# ProPrj_zmk-afa_2025-04-29.net
KiCad netlist of a schematic drawn in EasyEDA Pro
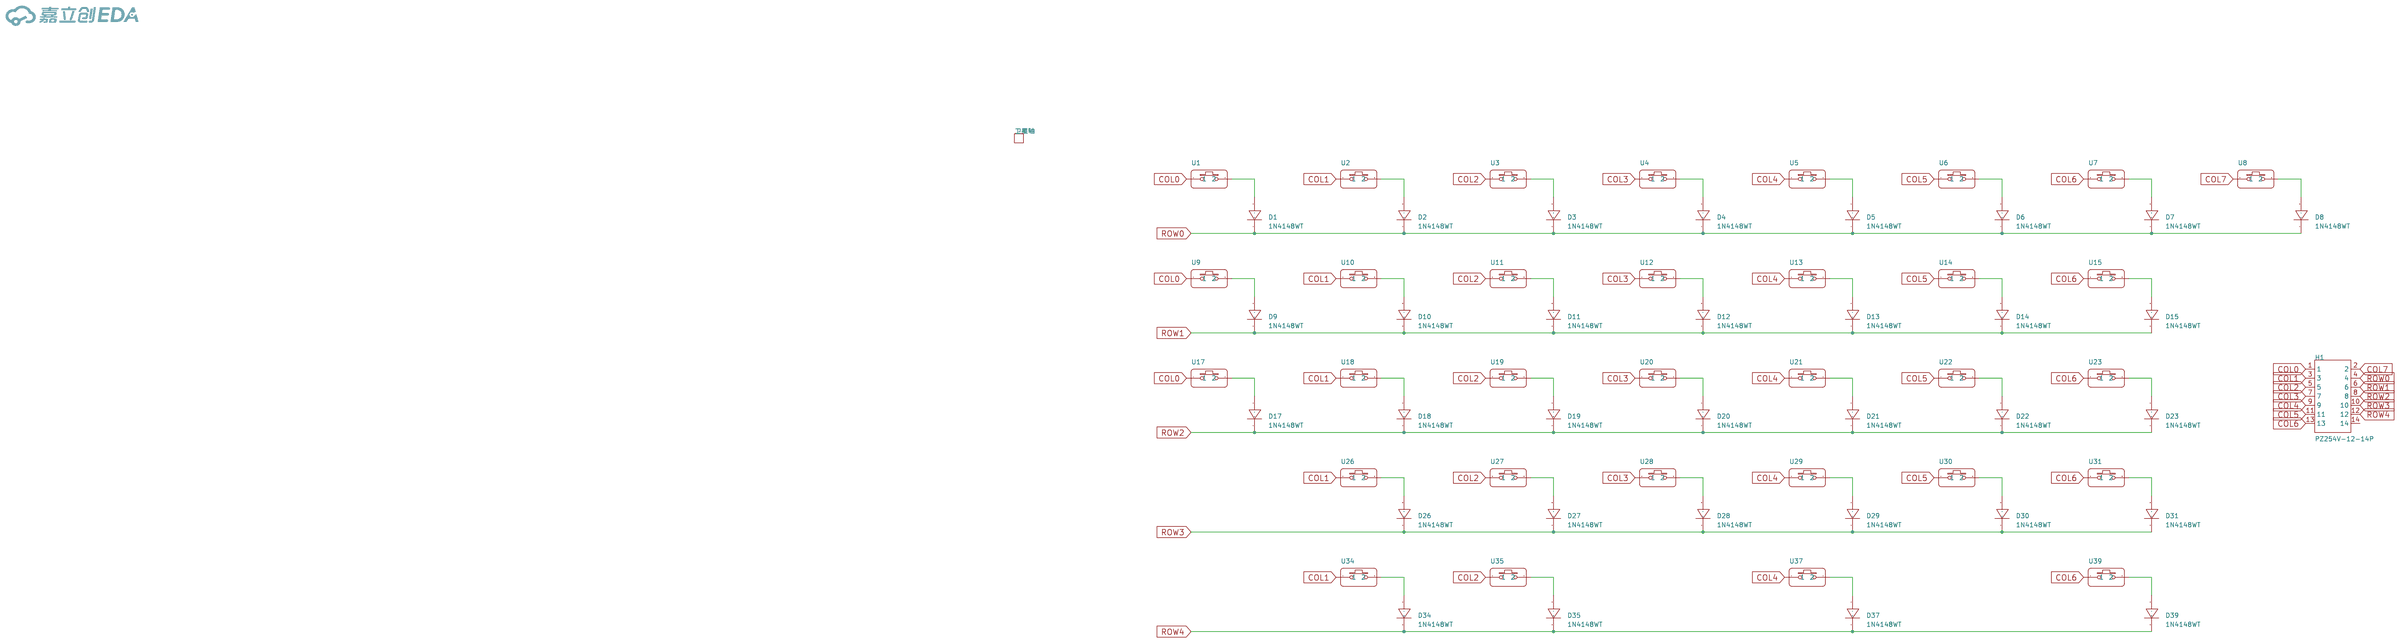
[diagram p0: schematic sheet]

(export (version "E")
  (design (tool "Eeschema 10.0.6"))
  (components
    (comp (ref "D1")
      (value "1N4148WT")
      (footprint "easyedapro:SOD-523_L1.2-W0.8-LS1.6-RD")
      (description "二极管配置:独立式;正向压降(Vf):1V@10mA;直流反向耐压(Vr):75V;整流电流:300mA;反向恢复时间(trr):4ns;")
      (fields (field (name "Manufacturer") "onsemi(安森美)"))
      (libsource (lib "easyedapro") (part "1N4148WT_C232841"))
    )
    (comp (ref "D2")
      (value "1N4148WT")
      (footprint "easyedapro:SOD-523_L1.2-W0.8-LS1.6-RD")
      (description "二极管配置:独立式;正向压降(Vf):1V@10mA;直流反向耐压(Vr):75V;整流电流:300mA;反向恢复时间(trr):4ns;")
      (fields (field (name "Manufacturer") "onsemi(安森美)"))
      (libsource (lib "easyedapro") (part "1N4148WT_C232841"))
    )
    (comp (ref "D3")
      (value "1N4148WT")
      (footprint "easyedapro:SOD-523_L1.2-W0.8-LS1.6-RD")
      (description "二极管配置:独立式;正向压降(Vf):1V@10mA;直流反向耐压(Vr):75V;整流电流:300mA;反向恢复时间(trr):4ns;")
      (fields (field (name "Manufacturer") "onsemi(安森美)"))
      (libsource (lib "easyedapro") (part "1N4148WT_C232841"))
    )
    (comp (ref "D4")
      (value "1N4148WT")
      (footprint "easyedapro:SOD-523_L1.2-W0.8-LS1.6-RD")
      (description "二极管配置:独立式;正向压降(Vf):1V@10mA;直流反向耐压(Vr):75V;整流电流:300mA;反向恢复时间(trr):4ns;")
      (fields (field (name "Manufacturer") "onsemi(安森美)"))
      (libsource (lib "easyedapro") (part "1N4148WT_C232841"))
    )
    (comp (ref "D5")
      (value "1N4148WT")
      (footprint "easyedapro:SOD-523_L1.2-W0.8-LS1.6-RD")
      (description "二极管配置:独立式;正向压降(Vf):1V@10mA;直流反向耐压(Vr):75V;整流电流:300mA;反向恢复时间(trr):4ns;")
      (fields (field (name "Manufacturer") "onsemi(安森美)"))
      (libsource (lib "easyedapro") (part "1N4148WT_C232841"))
    )
    (comp (ref "D6")
      (value "1N4148WT")
      (footprint "easyedapro:SOD-523_L1.2-W0.8-LS1.6-RD")
      (description "二极管配置:独立式;正向压降(Vf):1V@10mA;直流反向耐压(Vr):75V;整流电流:300mA;反向恢复时间(trr):4ns;")
      (fields (field (name "Manufacturer") "onsemi(安森美)"))
      (libsource (lib "easyedapro") (part "1N4148WT_C232841"))
    )
    (comp (ref "D7")
      (value "1N4148WT")
      (footprint "easyedapro:SOD-523_L1.2-W0.8-LS1.6-RD")
      (description "二极管配置:独立式;正向压降(Vf):1V@10mA;直流反向耐压(Vr):75V;整流电流:300mA;反向恢复时间(trr):4ns;")
      (fields (field (name "Manufacturer") "onsemi(安森美)"))
      (libsource (lib "easyedapro") (part "1N4148WT_C232841"))
    )
    (comp (ref "D8")
      (value "1N4148WT")
      (footprint "easyedapro:SOD-523_L1.2-W0.8-LS1.6-RD")
      (description "二极管配置:独立式;正向压降(Vf):1V@10mA;直流反向耐压(Vr):75V;整流电流:300mA;反向恢复时间(trr):4ns;")
      (fields (field (name "Manufacturer") "onsemi(安森美)"))
      (libsource (lib "easyedapro") (part "1N4148WT_C232841"))
    )
    (comp (ref "D9")
      (value "1N4148WT")
      (footprint "easyedapro:SOD-523_L1.2-W0.8-LS1.6-RD")
      (description "二极管配置:独立式;正向压降(Vf):1V@10mA;直流反向耐压(Vr):75V;整流电流:300mA;反向恢复时间(trr):4ns;")
      (fields (field (name "Manufacturer") "onsemi(安森美)"))
      (libsource (lib "easyedapro") (part "1N4148WT_C232841"))
    )
    (comp (ref "D10")
      (value "1N4148WT")
      (footprint "easyedapro:SOD-523_L1.2-W0.8-LS1.6-RD")
      (description "二极管配置:独立式;正向压降(Vf):1V@10mA;直流反向耐压(Vr):75V;整流电流:300mA;反向恢复时间(trr):4ns;")
      (fields (field (name "Manufacturer") "onsemi(安森美)"))
      (libsource (lib "easyedapro") (part "1N4148WT_C232841"))
    )
    (comp (ref "D11")
      (value "1N4148WT")
      (footprint "easyedapro:SOD-523_L1.2-W0.8-LS1.6-RD")
      (description "二极管配置:独立式;正向压降(Vf):1V@10mA;直流反向耐压(Vr):75V;整流电流:300mA;反向恢复时间(trr):4ns;")
      (fields (field (name "Manufacturer") "onsemi(安森美)"))
      (libsource (lib "easyedapro") (part "1N4148WT_C232841"))
    )
    (comp (ref "D12")
      (value "1N4148WT")
      (footprint "easyedapro:SOD-523_L1.2-W0.8-LS1.6-RD")
      (description "二极管配置:独立式;正向压降(Vf):1V@10mA;直流反向耐压(Vr):75V;整流电流:300mA;反向恢复时间(trr):4ns;")
      (fields (field (name "Manufacturer") "onsemi(安森美)"))
      (libsource (lib "easyedapro") (part "1N4148WT_C232841"))
    )
    (comp (ref "D13")
      (value "1N4148WT")
      (footprint "easyedapro:SOD-523_L1.2-W0.8-LS1.6-RD")
      (description "二极管配置:独立式;正向压降(Vf):1V@10mA;直流反向耐压(Vr):75V;整流电流:300mA;反向恢复时间(trr):4ns;")
      (fields (field (name "Manufacturer") "onsemi(安森美)"))
      (libsource (lib "easyedapro") (part "1N4148WT_C232841"))
    )
    (comp (ref "D14")
      (value "1N4148WT")
      (footprint "easyedapro:SOD-523_L1.2-W0.8-LS1.6-RD")
      (description "二极管配置:独立式;正向压降(Vf):1V@10mA;直流反向耐压(Vr):75V;整流电流:300mA;反向恢复时间(trr):4ns;")
      (fields (field (name "Manufacturer") "onsemi(安森美)"))
      (libsource (lib "easyedapro") (part "1N4148WT_C232841"))
    )
    (comp (ref "D15")
      (value "1N4148WT")
      (footprint "easyedapro:SOD-523_L1.2-W0.8-LS1.6-RD")
      (description "二极管配置:独立式;正向压降(Vf):1V@10mA;直流反向耐压(Vr):75V;整流电流:300mA;反向恢复时间(trr):4ns;")
      (fields (field (name "Manufacturer") "onsemi(安森美)"))
      (libsource (lib "easyedapro") (part "1N4148WT_C232841"))
    )
    (comp (ref "D17")
      (value "1N4148WT")
      (footprint "easyedapro:SOD-523_L1.2-W0.8-LS1.6-RD")
      (description "二极管配置:独立式;正向压降(Vf):1V@10mA;直流反向耐压(Vr):75V;整流电流:300mA;反向恢复时间(trr):4ns;")
      (fields (field (name "Manufacturer") "onsemi(安森美)"))
      (libsource (lib "easyedapro") (part "1N4148WT_C232841"))
    )
    (comp (ref "D18")
      (value "1N4148WT")
      (footprint "easyedapro:SOD-523_L1.2-W0.8-LS1.6-RD")
      (description "二极管配置:独立式;正向压降(Vf):1V@10mA;直流反向耐压(Vr):75V;整流电流:300mA;反向恢复时间(trr):4ns;")
      (fields (field (name "Manufacturer") "onsemi(安森美)"))
      (libsource (lib "easyedapro") (part "1N4148WT_C232841"))
    )
    (comp (ref "D19")
      (value "1N4148WT")
      (footprint "easyedapro:SOD-523_L1.2-W0.8-LS1.6-RD")
      (description "二极管配置:独立式;正向压降(Vf):1V@10mA;直流反向耐压(Vr):75V;整流电流:300mA;反向恢复时间(trr):4ns;")
      (fields (field (name "Manufacturer") "onsemi(安森美)"))
      (libsource (lib "easyedapro") (part "1N4148WT_C232841"))
    )
    (comp (ref "D20")
      (value "1N4148WT")
      (footprint "easyedapro:SOD-523_L1.2-W0.8-LS1.6-RD")
      (description "二极管配置:独立式;正向压降(Vf):1V@10mA;直流反向耐压(Vr):75V;整流电流:300mA;反向恢复时间(trr):4ns;")
      (fields (field (name "Manufacturer") "onsemi(安森美)"))
      (libsource (lib "easyedapro") (part "1N4148WT_C232841"))
    )
    (comp (ref "D21")
      (value "1N4148WT")
      (footprint "easyedapro:SOD-523_L1.2-W0.8-LS1.6-RD")
      (description "二极管配置:独立式;正向压降(Vf):1V@10mA;直流反向耐压(Vr):75V;整流电流:300mA;反向恢复时间(trr):4ns;")
      (fields (field (name "Manufacturer") "onsemi(安森美)"))
      (libsource (lib "easyedapro") (part "1N4148WT_C232841"))
    )
    (comp (ref "D22")
      (value "1N4148WT")
      (footprint "easyedapro:SOD-523_L1.2-W0.8-LS1.6-RD")
      (description "二极管配置:独立式;正向压降(Vf):1V@10mA;直流反向耐压(Vr):75V;整流电流:300mA;反向恢复时间(trr):4ns;")
      (fields (field (name "Manufacturer") "onsemi(安森美)"))
      (libsource (lib "easyedapro") (part "1N4148WT_C232841"))
    )
    (comp (ref "D23")
      (value "1N4148WT")
      (footprint "easyedapro:SOD-523_L1.2-W0.8-LS1.6-RD")
      (description "二极管配置:独立式;正向压降(Vf):1V@10mA;直流反向耐压(Vr):75V;整流电流:300mA;反向恢复时间(trr):4ns;")
      (fields (field (name "Manufacturer") "onsemi(安森美)"))
      (libsource (lib "easyedapro") (part "1N4148WT_C232841"))
    )
    (comp (ref "D26")
      (value "1N4148WT")
      (footprint "easyedapro:SOD-523_L1.2-W0.8-LS1.6-RD")
      (description "二极管配置:独立式;正向压降(Vf):1V@10mA;直流反向耐压(Vr):75V;整流电流:300mA;反向恢复时间(trr):4ns;")
      (fields (field (name "Manufacturer") "onsemi(安森美)"))
      (libsource (lib "easyedapro") (part "1N4148WT_C232841"))
    )
    (comp (ref "D27")
      (value "1N4148WT")
      (footprint "easyedapro:SOD-523_L1.2-W0.8-LS1.6-RD")
      (description "二极管配置:独立式;正向压降(Vf):1V@10mA;直流反向耐压(Vr):75V;整流电流:300mA;反向恢复时间(trr):4ns;")
      (fields (field (name "Manufacturer") "onsemi(安森美)"))
      (libsource (lib "easyedapro") (part "1N4148WT_C232841"))
    )
    (comp (ref "D28")
      (value "1N4148WT")
      (footprint "easyedapro:SOD-523_L1.2-W0.8-LS1.6-RD")
      (description "二极管配置:独立式;正向压降(Vf):1V@10mA;直流反向耐压(Vr):75V;整流电流:300mA;反向恢复时间(trr):4ns;")
      (fields (field (name "Manufacturer") "onsemi(安森美)"))
      (libsource (lib "easyedapro") (part "1N4148WT_C232841"))
    )
    (comp (ref "D29")
      (value "1N4148WT")
      (footprint "easyedapro:SOD-523_L1.2-W0.8-LS1.6-RD")
      (description "二极管配置:独立式;正向压降(Vf):1V@10mA;直流反向耐压(Vr):75V;整流电流:300mA;反向恢复时间(trr):4ns;")
      (fields (field (name "Manufacturer") "onsemi(安森美)"))
      (libsource (lib "easyedapro") (part "1N4148WT_C232841"))
    )
    (comp (ref "D30")
      (value "1N4148WT")
      (footprint "easyedapro:SOD-523_L1.2-W0.8-LS1.6-RD")
      (description "二极管配置:独立式;正向压降(Vf):1V@10mA;直流反向耐压(Vr):75V;整流电流:300mA;反向恢复时间(trr):4ns;")
      (fields (field (name "Manufacturer") "onsemi(安森美)"))
      (libsource (lib "easyedapro") (part "1N4148WT_C232841"))
    )
    (comp (ref "D31")
      (value "1N4148WT")
      (footprint "easyedapro:SOD-523_L1.2-W0.8-LS1.6-RD")
      (description "二极管配置:独立式;正向压降(Vf):1V@10mA;直流反向耐压(Vr):75V;整流电流:300mA;反向恢复时间(trr):4ns;")
      (fields (field (name "Manufacturer") "onsemi(安森美)"))
      (libsource (lib "easyedapro") (part "1N4148WT_C232841"))
    )
    (comp (ref "D34")
      (value "1N4148WT")
      (footprint "easyedapro:SOD-523_L1.2-W0.8-LS1.6-RD")
      (description "二极管配置:独立式;正向压降(Vf):1V@10mA;直流反向耐压(Vr):75V;整流电流:300mA;反向恢复时间(trr):4ns;")
      (fields (field (name "Manufacturer") "onsemi(安森美)"))
      (libsource (lib "easyedapro") (part "1N4148WT_C232841"))
    )
    (comp (ref "D35")
      (value "1N4148WT")
      (footprint "easyedapro:SOD-523_L1.2-W0.8-LS1.6-RD")
      (description "二极管配置:独立式;正向压降(Vf):1V@10mA;直流反向耐压(Vr):75V;整流电流:300mA;反向恢复时间(trr):4ns;")
      (fields (field (name "Manufacturer") "onsemi(安森美)"))
      (libsource (lib "easyedapro") (part "1N4148WT_C232841"))
    )
    (comp (ref "D37")
      (value "1N4148WT")
      (footprint "easyedapro:SOD-523_L1.2-W0.8-LS1.6-RD")
      (description "二极管配置:独立式;正向压降(Vf):1V@10mA;直流反向耐压(Vr):75V;整流电流:300mA;反向恢复时间(trr):4ns;")
      (fields (field (name "Manufacturer") "onsemi(安森美)"))
      (libsource (lib "easyedapro") (part "1N4148WT_C232841"))
    )
    (comp (ref "D39")
      (value "1N4148WT")
      (footprint "easyedapro:SOD-523_L1.2-W0.8-LS1.6-RD")
      (description "二极管配置:独立式;正向压降(Vf):1V@10mA;直流反向耐压(Vr):75V;整流电流:300mA;反向恢复时间(trr):4ns;")
      (fields (field (name "Manufacturer") "onsemi(安森美)"))
      (libsource (lib "easyedapro") (part "1N4148WT_C232841"))
    )
    (comp (ref "H1")
      (value "PZ254V-12-14P")
      (footprint "easyedapro:HDR-TH_14P-P2.54-V-M-R2-C7-S2.54")
      (fields (field (name "Manufacturer") "XFCN(兴飞)"))
      (libsource (lib "easyedapro") (part "PZ254V-12-14P"))
    )
    (comp (ref "U1")
      (value "~")
      (footprint "easyedapro:两用轴座无灯")
      (libsource (lib "easyedapro") (part "两用轴座无灯"))
    )
    (comp (ref "U2")
      (value "~")
      (footprint "easyedapro:两用轴座无灯")
      (libsource (lib "easyedapro") (part "两用轴座无灯"))
    )
    (comp (ref "U3")
      (value "~")
      (footprint "easyedapro:两用轴座无灯")
      (libsource (lib "easyedapro") (part "两用轴座无灯"))
    )
    (comp (ref "U4")
      (value "~")
      (footprint "easyedapro:两用轴座无灯")
      (libsource (lib "easyedapro") (part "两用轴座无灯"))
    )
    (comp (ref "U5")
      (value "~")
      (footprint "easyedapro:两用轴座无灯")
      (libsource (lib "easyedapro") (part "两用轴座无灯"))
    )
    (comp (ref "U6")
      (value "~")
      (footprint "easyedapro:两用轴座无灯")
      (libsource (lib "easyedapro") (part "两用轴座无灯"))
    )
    (comp (ref "U7")
      (value "~")
      (footprint "easyedapro:两用轴座无灯")
      (libsource (lib "easyedapro") (part "两用轴座无灯"))
    )
    (comp (ref "U8")
      (value "~")
      (footprint "easyedapro:两用轴座无灯")
      (libsource (lib "easyedapro") (part "两用轴座无灯"))
    )
    (comp (ref "U9")
      (value "~")
      (footprint "easyedapro:两用轴座无灯")
      (libsource (lib "easyedapro") (part "两用轴座无灯"))
    )
    (comp (ref "U10")
      (value "~")
      (footprint "easyedapro:两用轴座无灯")
      (libsource (lib "easyedapro") (part "两用轴座无灯"))
    )
    (comp (ref "U11")
      (value "~")
      (footprint "easyedapro:两用轴座无灯")
      (libsource (lib "easyedapro") (part "两用轴座无灯"))
    )
    (comp (ref "U12")
      (value "~")
      (footprint "easyedapro:两用轴座无灯")
      (libsource (lib "easyedapro") (part "两用轴座无灯"))
    )
    (comp (ref "U13")
      (value "~")
      (footprint "easyedapro:两用轴座无灯")
      (libsource (lib "easyedapro") (part "两用轴座无灯"))
    )
    (comp (ref "U14")
      (value "~")
      (footprint "easyedapro:两用轴座无灯")
      (libsource (lib "easyedapro") (part "两用轴座无灯"))
    )
    (comp (ref "U15")
      (value "~")
      (footprint "easyedapro:两用轴座无灯")
      (libsource (lib "easyedapro") (part "两用轴座无灯"))
    )
    (comp (ref "U17")
      (value "~")
      (footprint "easyedapro:两用轴座无灯")
      (libsource (lib "easyedapro") (part "两用轴座无灯"))
    )
    (comp (ref "U18")
      (value "~")
      (footprint "easyedapro:两用轴座无灯")
      (libsource (lib "easyedapro") (part "两用轴座无灯"))
    )
    (comp (ref "U19")
      (value "~")
      (footprint "easyedapro:两用轴座无灯")
      (libsource (lib "easyedapro") (part "两用轴座无灯"))
    )
    (comp (ref "U20")
      (value "~")
      (footprint "easyedapro:两用轴座无灯")
      (libsource (lib "easyedapro") (part "两用轴座无灯"))
    )
    (comp (ref "U21")
      (value "~")
      (footprint "easyedapro:两用轴座无灯")
      (libsource (lib "easyedapro") (part "两用轴座无灯"))
    )
    (comp (ref "U22")
      (value "~")
      (footprint "easyedapro:两用轴座无灯")
      (libsource (lib "easyedapro") (part "两用轴座无灯"))
    )
    (comp (ref "U23")
      (value "~")
      (footprint "easyedapro:两用轴座无灯")
      (libsource (lib "easyedapro") (part "两用轴座无灯"))
    )
    (comp (ref "U26")
      (value "~")
      (footprint "easyedapro:两用轴座无灯")
      (libsource (lib "easyedapro") (part "两用轴座无灯"))
    )
    (comp (ref "U27")
      (value "~")
      (footprint "easyedapro:两用轴座无灯")
      (libsource (lib "easyedapro") (part "两用轴座无灯"))
    )
    (comp (ref "U28")
      (value "~")
      (footprint "easyedapro:两用轴座无灯")
      (libsource (lib "easyedapro") (part "两用轴座无灯"))
    )
    (comp (ref "U29")
      (value "~")
      (footprint "easyedapro:两用轴座无灯")
      (libsource (lib "easyedapro") (part "两用轴座无灯"))
    )
    (comp (ref "U30")
      (value "~")
      (footprint "easyedapro:两用轴座无灯")
      (libsource (lib "easyedapro") (part "两用轴座无灯"))
    )
    (comp (ref "U31")
      (value "~")
      (footprint "easyedapro:两用轴座无灯")
      (libsource (lib "easyedapro") (part "两用轴座无灯"))
    )
    (comp (ref "U34")
      (value "~")
      (footprint "easyedapro:两用轴座无灯")
      (libsource (lib "easyedapro") (part "两用轴座无灯"))
    )
    (comp (ref "U35")
      (value "~")
      (footprint "easyedapro:两用轴座无灯")
      (libsource (lib "easyedapro") (part "两用轴座无灯"))
    )
    (comp (ref "U37")
      (value "~")
      (footprint "easyedapro:两用轴座无灯")
      (libsource (lib "easyedapro") (part "两用轴座无灯"))
    )
    (comp (ref "U39")
      (value "~")
      (footprint "easyedapro:两用轴座无灯")
      (libsource (lib "easyedapro") (part "两用轴座无灯"))
    )
    (comp (ref "卫星轴") (value "~") (footprint "easyedapro:卫星轴") (libsource (lib "easyedapro") (part "卫星轴")))
  )
  (nets
    (net (code "1") (name "COL0") (class "Default")
      (node (ref "H1") (pin "1") (pinfunction "1_1") (pintype "unspecified"))
      (node (ref "U1") (pin "1") (pinfunction "1_1") (pintype "input"))
      (node (ref "U17") (pin "1") (pinfunction "1_1") (pintype "input"))
      (node (ref "U9") (pin "1") (pinfunction "1_1") (pintype "input"))
    )
    (net (code "2") (name "COL1") (class "Default")
      (node (ref "H1") (pin "3") (pinfunction "3_3") (pintype "unspecified"))
      (node (ref "U10") (pin "1") (pinfunction "1_1") (pintype "input"))
      (node (ref "U18") (pin "1") (pinfunction "1_1") (pintype "input"))
      (node (ref "U2") (pin "1") (pinfunction "1_1") (pintype "input"))
      (node (ref "U26") (pin "1") (pinfunction "1_1") (pintype "input"))
      (node (ref "U34") (pin "1") (pinfunction "1_1") (pintype "input"))
    )
    (net (code "3") (name "COL2") (class "Default")
      (node (ref "H1") (pin "5") (pinfunction "5_5") (pintype "unspecified"))
      (node (ref "U11") (pin "1") (pinfunction "1_1") (pintype "input"))
      (node (ref "U19") (pin "1") (pinfunction "1_1") (pintype "input"))
      (node (ref "U27") (pin "1") (pinfunction "1_1") (pintype "input"))
      (node (ref "U3") (pin "1") (pinfunction "1_1") (pintype "input"))
      (node (ref "U35") (pin "1") (pinfunction "1_1") (pintype "input"))
    )
    (net (code "4") (name "COL3") (class "Default")
      (node (ref "H1") (pin "7") (pinfunction "7_7") (pintype "unspecified"))
      (node (ref "U12") (pin "1") (pinfunction "1_1") (pintype "input"))
      (node (ref "U20") (pin "1") (pinfunction "1_1") (pintype "input"))
      (node (ref "U28") (pin "1") (pinfunction "1_1") (pintype "input"))
      (node (ref "U4") (pin "1") (pinfunction "1_1") (pintype "input"))
    )
    (net (code "5") (name "COL4") (class "Default")
      (node (ref "H1") (pin "9") (pinfunction "9_9") (pintype "unspecified"))
      (node (ref "U13") (pin "1") (pinfunction "1_1") (pintype "input"))
      (node (ref "U21") (pin "1") (pinfunction "1_1") (pintype "input"))
      (node (ref "U29") (pin "1") (pinfunction "1_1") (pintype "input"))
      (node (ref "U37") (pin "1") (pinfunction "1_1") (pintype "input"))
      (node (ref "U5") (pin "1") (pinfunction "1_1") (pintype "input"))
    )
    (net (code "6") (name "COL5") (class "Default")
      (node (ref "H1") (pin "11") (pinfunction "11_11") (pintype "unspecified"))
      (node (ref "U14") (pin "1") (pinfunction "1_1") (pintype "input"))
      (node (ref "U22") (pin "1") (pinfunction "1_1") (pintype "input"))
      (node (ref "U30") (pin "1") (pinfunction "1_1") (pintype "input"))
      (node (ref "U6") (pin "1") (pinfunction "1_1") (pintype "input"))
    )
    (net (code "7") (name "COL6") (class "Default")
      (node (ref "H1") (pin "13") (pinfunction "13_13") (pintype "unspecified"))
      (node (ref "U15") (pin "1") (pinfunction "1_1") (pintype "input"))
      (node (ref "U23") (pin "1") (pinfunction "1_1") (pintype "input"))
      (node (ref "U31") (pin "1") (pinfunction "1_1") (pintype "input"))
      (node (ref "U39") (pin "1") (pinfunction "1_1") (pintype "input"))
      (node (ref "U7") (pin "1") (pinfunction "1_1") (pintype "input"))
    )
    (net (code "8") (name "COL7") (class "Default")
      (node (ref "H1") (pin "2") (pinfunction "2_2") (pintype "unspecified"))
      (node (ref "U8") (pin "1") (pinfunction "1_1") (pintype "input"))
    )
    (net (code "9") (name "Net-(D1-A)") (class "Default")
      (node (ref "D1") (pin "2") (pinfunction "A_2") (pintype "unspecified"))
      (node (ref "U1") (pin "2") (pinfunction "2_2") (pintype "input"))
    )
    (net (code "10") (name "Net-(D2-A)") (class "Default")
      (node (ref "D2") (pin "2") (pinfunction "A_2") (pintype "unspecified"))
      (node (ref "U2") (pin "2") (pinfunction "2_2") (pintype "input"))
    )
    (net (code "11") (name "Net-(D3-A)") (class "Default")
      (node (ref "D3") (pin "2") (pinfunction "A_2") (pintype "unspecified"))
      (node (ref "U3") (pin "2") (pinfunction "2_2") (pintype "input"))
    )
    (net (code "12") (name "Net-(D4-A)") (class "Default")
      (node (ref "D4") (pin "2") (pinfunction "A_2") (pintype "unspecified"))
      (node (ref "U4") (pin "2") (pinfunction "2_2") (pintype "input"))
    )
    (net (code "13") (name "Net-(D5-A)") (class "Default")
      (node (ref "D5") (pin "2") (pinfunction "A_2") (pintype "unspecified"))
      (node (ref "U5") (pin "2") (pinfunction "2_2") (pintype "input"))
    )
    (net (code "14") (name "Net-(D6-A)") (class "Default")
      (node (ref "D6") (pin "2") (pinfunction "A_2") (pintype "unspecified"))
      (node (ref "U6") (pin "2") (pinfunction "2_2") (pintype "input"))
    )
    (net (code "15") (name "Net-(D7-A)") (class "Default")
      (node (ref "D7") (pin "2") (pinfunction "A_2") (pintype "unspecified"))
      (node (ref "U7") (pin "2") (pinfunction "2_2") (pintype "input"))
    )
    (net (code "16") (name "Net-(D8-A)") (class "Default")
      (node (ref "D8") (pin "2") (pinfunction "A_2") (pintype "unspecified"))
      (node (ref "U8") (pin "2") (pinfunction "2_2") (pintype "input"))
    )
    (net (code "17") (name "Net-(D9-A)") (class "Default")
      (node (ref "D9") (pin "2") (pinfunction "A_2") (pintype "unspecified"))
      (node (ref "U9") (pin "2") (pinfunction "2_2") (pintype "input"))
    )
    (net (code "18") (name "Net-(D10-A)") (class "Default")
      (node (ref "D10") (pin "2") (pinfunction "A_2") (pintype "unspecified"))
      (node (ref "U10") (pin "2") (pinfunction "2_2") (pintype "input"))
    )
    (net (code "19") (name "Net-(D11-A)") (class "Default")
      (node (ref "D11") (pin "2") (pinfunction "A_2") (pintype "unspecified"))
      (node (ref "U11") (pin "2") (pinfunction "2_2") (pintype "input"))
    )
    (net (code "20") (name "Net-(D12-A)") (class "Default")
      (node (ref "D12") (pin "2") (pinfunction "A_2") (pintype "unspecified"))
      (node (ref "U12") (pin "2") (pinfunction "2_2") (pintype "input"))
    )
    (net (code "21") (name "Net-(D13-A)") (class "Default")
      (node (ref "D13") (pin "2") (pinfunction "A_2") (pintype "unspecified"))
      (node (ref "U13") (pin "2") (pinfunction "2_2") (pintype "input"))
    )
    (net (code "22") (name "Net-(D14-A)") (class "Default")
      (node (ref "D14") (pin "2") (pinfunction "A_2") (pintype "unspecified"))
      (node (ref "U14") (pin "2") (pinfunction "2_2") (pintype "input"))
    )
    (net (code "23") (name "Net-(D15-A)") (class "Default")
      (node (ref "D15") (pin "2") (pinfunction "A_2") (pintype "unspecified"))
      (node (ref "U15") (pin "2") (pinfunction "2_2") (pintype "input"))
    )
    (net (code "24") (name "Net-(D17-A)") (class "Default")
      (node (ref "D17") (pin "2") (pinfunction "A_2") (pintype "unspecified"))
      (node (ref "U17") (pin "2") (pinfunction "2_2") (pintype "input"))
    )
    (net (code "25") (name "Net-(D18-A)") (class "Default")
      (node (ref "D18") (pin "2") (pinfunction "A_2") (pintype "unspecified"))
      (node (ref "U18") (pin "2") (pinfunction "2_2") (pintype "input"))
    )
    (net (code "26") (name "Net-(D19-A)") (class "Default")
      (node (ref "D19") (pin "2") (pinfunction "A_2") (pintype "unspecified"))
      (node (ref "U19") (pin "2") (pinfunction "2_2") (pintype "input"))
    )
    (net (code "27") (name "Net-(D20-A)") (class "Default")
      (node (ref "D20") (pin "2") (pinfunction "A_2") (pintype "unspecified"))
      (node (ref "U20") (pin "2") (pinfunction "2_2") (pintype "input"))
    )
    (net (code "28") (name "Net-(D21-A)") (class "Default")
      (node (ref "D21") (pin "2") (pinfunction "A_2") (pintype "unspecified"))
      (node (ref "U21") (pin "2") (pinfunction "2_2") (pintype "input"))
    )
    (net (code "29") (name "Net-(D22-A)") (class "Default")
      (node (ref "D22") (pin "2") (pinfunction "A_2") (pintype "unspecified"))
      (node (ref "U22") (pin "2") (pinfunction "2_2") (pintype "input"))
    )
    (net (code "30") (name "Net-(D23-A)") (class "Default")
      (node (ref "D23") (pin "2") (pinfunction "A_2") (pintype "unspecified"))
      (node (ref "U23") (pin "2") (pinfunction "2_2") (pintype "input"))
    )
    (net (code "31") (name "Net-(D26-A)") (class "Default")
      (node (ref "D26") (pin "2") (pinfunction "A_2") (pintype "unspecified"))
      (node (ref "U26") (pin "2") (pinfunction "2_2") (pintype "input"))
    )
    (net (code "32") (name "Net-(D27-A)") (class "Default")
      (node (ref "D27") (pin "2") (pinfunction "A_2") (pintype "unspecified"))
      (node (ref "U27") (pin "2") (pinfunction "2_2") (pintype "input"))
    )
    (net (code "33") (name "Net-(D28-A)") (class "Default")
      (node (ref "D28") (pin "2") (pinfunction "A_2") (pintype "unspecified"))
      (node (ref "U28") (pin "2") (pinfunction "2_2") (pintype "input"))
    )
    (net (code "34") (name "Net-(D29-A)") (class "Default")
      (node (ref "D29") (pin "2") (pinfunction "A_2") (pintype "unspecified"))
      (node (ref "U29") (pin "2") (pinfunction "2_2") (pintype "input"))
    )
    (net (code "35") (name "Net-(D30-A)") (class "Default")
      (node (ref "D30") (pin "2") (pinfunction "A_2") (pintype "unspecified"))
      (node (ref "U30") (pin "2") (pinfunction "2_2") (pintype "input"))
    )
    (net (code "36") (name "Net-(D31-A)") (class "Default")
      (node (ref "D31") (pin "2") (pinfunction "A_2") (pintype "unspecified"))
      (node (ref "U31") (pin "2") (pinfunction "2_2") (pintype "input"))
    )
    (net (code "37") (name "Net-(D34-A)") (class "Default")
      (node (ref "D34") (pin "2") (pinfunction "A_2") (pintype "unspecified"))
      (node (ref "U34") (pin "2") (pinfunction "2_2") (pintype "input"))
    )
    (net (code "38") (name "Net-(D35-A)") (class "Default")
      (node (ref "D35") (pin "2") (pinfunction "A_2") (pintype "unspecified"))
      (node (ref "U35") (pin "2") (pinfunction "2_2") (pintype "input"))
    )
    (net (code "39") (name "Net-(D37-A)") (class "Default")
      (node (ref "D37") (pin "2") (pinfunction "A_2") (pintype "unspecified"))
      (node (ref "U37") (pin "2") (pinfunction "2_2") (pintype "input"))
    )
    (net (code "40") (name "Net-(D39-A)") (class "Default")
      (node (ref "D39") (pin "2") (pinfunction "A_2") (pintype "unspecified"))
      (node (ref "U39") (pin "2") (pinfunction "2_2") (pintype "input"))
    )
    (net (code "41") (name "ROW0") (class "Default")
      (node (ref "D1") (pin "1") (pinfunction "C_1") (pintype "unspecified"))
      (node (ref "D2") (pin "1") (pinfunction "C_1") (pintype "unspecified"))
      (node (ref "D3") (pin "1") (pinfunction "C_1") (pintype "unspecified"))
      (node (ref "D4") (pin "1") (pinfunction "C_1") (pintype "unspecified"))
      (node (ref "D5") (pin "1") (pinfunction "C_1") (pintype "unspecified"))
      (node (ref "D6") (pin "1") (pinfunction "C_1") (pintype "unspecified"))
      (node (ref "D7") (pin "1") (pinfunction "C_1") (pintype "unspecified"))
      (node (ref "D8") (pin "1") (pinfunction "C_1") (pintype "unspecified"))
      (node (ref "H1") (pin "4") (pinfunction "4_4") (pintype "unspecified"))
    )
    (net (code "42") (name "ROW1") (class "Default")
      (node (ref "D10") (pin "1") (pinfunction "C_1") (pintype "unspecified"))
      (node (ref "D11") (pin "1") (pinfunction "C_1") (pintype "unspecified"))
      (node (ref "D12") (pin "1") (pinfunction "C_1") (pintype "unspecified"))
      (node (ref "D13") (pin "1") (pinfunction "C_1") (pintype "unspecified"))
      (node (ref "D14") (pin "1") (pinfunction "C_1") (pintype "unspecified"))
      (node (ref "D15") (pin "1") (pinfunction "C_1") (pintype "unspecified"))
      (node (ref "D9") (pin "1") (pinfunction "C_1") (pintype "unspecified"))
      (node (ref "H1") (pin "6") (pinfunction "6_6") (pintype "unspecified"))
    )
    (net (code "43") (name "ROW2") (class "Default")
      (node (ref "D17") (pin "1") (pinfunction "C_1") (pintype "unspecified"))
      (node (ref "D18") (pin "1") (pinfunction "C_1") (pintype "unspecified"))
      (node (ref "D19") (pin "1") (pinfunction "C_1") (pintype "unspecified"))
      (node (ref "D20") (pin "1") (pinfunction "C_1") (pintype "unspecified"))
      (node (ref "D21") (pin "1") (pinfunction "C_1") (pintype "unspecified"))
      (node (ref "D22") (pin "1") (pinfunction "C_1") (pintype "unspecified"))
      (node (ref "D23") (pin "1") (pinfunction "C_1") (pintype "unspecified"))
      (node (ref "H1") (pin "8") (pinfunction "8_8") (pintype "unspecified"))
    )
    (net (code "44") (name "ROW3") (class "Default")
      (node (ref "D26") (pin "1") (pinfunction "C_1") (pintype "unspecified"))
      (node (ref "D27") (pin "1") (pinfunction "C_1") (pintype "unspecified"))
      (node (ref "D28") (pin "1") (pinfunction "C_1") (pintype "unspecified"))
      (node (ref "D29") (pin "1") (pinfunction "C_1") (pintype "unspecified"))
      (node (ref "D30") (pin "1") (pinfunction "C_1") (pintype "unspecified"))
      (node (ref "D31") (pin "1") (pinfunction "C_1") (pintype "unspecified"))
      (node (ref "H1") (pin "10") (pinfunction "10_10") (pintype "unspecified"))
    )
    (net (code "45") (name "ROW4") (class "Default")
      (node (ref "D34") (pin "1") (pinfunction "C_1") (pintype "unspecified"))
      (node (ref "D35") (pin "1") (pinfunction "C_1") (pintype "unspecified"))
      (node (ref "D37") (pin "1") (pinfunction "C_1") (pintype "unspecified"))
      (node (ref "D39") (pin "1") (pinfunction "C_1") (pintype "unspecified"))
      (node (ref "H1") (pin "12") (pinfunction "12_12") (pintype "unspecified"))
    )
    (net (code "46") (name "unconnected-(H1-Pad14)") (class "Default")
      (node (ref "H1") (pin "14") (pinfunction "14_14") (pintype "unspecified"))
    )
  )
)
